# ad_1.net
KiCad netlist of a schematic drawn in Altium Designer
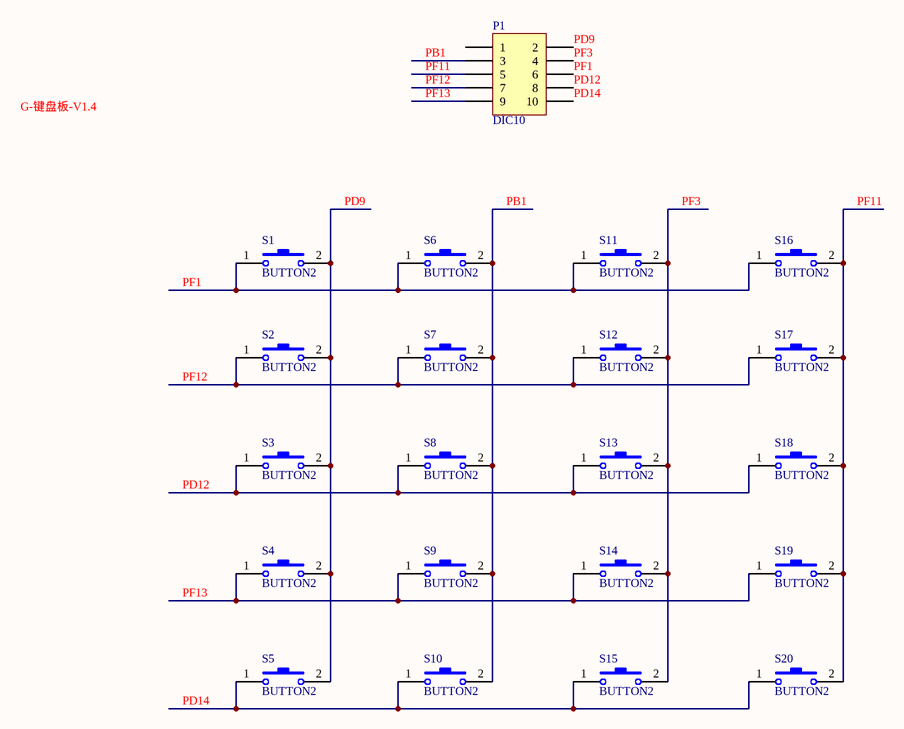
[diagram p0: ad_1.schdoc]

(export (version "E")
  (design (tool "Eeschema 10.0.6"))
  (components
    (comp (ref "P1")
      (value "DIC10")
      (description "连接器")
      (fields (field (name "PUBLISHER") "Altium Limited"))
      (libsource (lib "base") (part "DIC10"))
    )
    (comp (ref "S1")
      (value "BUTTON2")
      (footprint "BUTTON-SMD-7*7")
      (description "按钮")
      (fields (field (name "PUBLISHER") "Altium Limited"))
      (libsource (lib "base") (part "BUTTON2"))
    )
    (comp (ref "S2")
      (value "BUTTON2")
      (footprint "BUTTON-SMD-7*7")
      (description "按钮")
      (fields (field (name "PUBLISHER") "Altium Limited"))
      (libsource (lib "base") (part "BUTTON2"))
    )
    (comp (ref "S3")
      (value "BUTTON2")
      (footprint "BUTTON-SMD-7*7")
      (description "按钮")
      (fields (field (name "PUBLISHER") "Altium Limited"))
      (libsource (lib "base") (part "BUTTON2"))
    )
    (comp (ref "S4")
      (value "BUTTON2")
      (footprint "BUTTON-SMD-7*7")
      (description "按钮")
      (fields (field (name "PUBLISHER") "Altium Limited"))
      (libsource (lib "base") (part "BUTTON2"))
    )
    (comp (ref "S5")
      (value "BUTTON2")
      (footprint "BUTTON-SMD-7*7")
      (description "按钮")
      (fields (field (name "PUBLISHER") "Altium Limited"))
      (libsource (lib "base") (part "BUTTON2"))
    )
    (comp (ref "S6")
      (value "BUTTON2")
      (footprint "BUTTON-SMD-7*7")
      (description "按钮")
      (fields (field (name "PUBLISHER") "Altium Limited"))
      (libsource (lib "base") (part "BUTTON2"))
    )
    (comp (ref "S7")
      (value "BUTTON2")
      (footprint "BUTTON-SMD-7*7")
      (description "按钮")
      (fields (field (name "PUBLISHER") "Altium Limited"))
      (libsource (lib "base") (part "BUTTON2"))
    )
    (comp (ref "S8")
      (value "BUTTON2")
      (footprint "BUTTON-SMD-7*7")
      (description "按钮")
      (fields (field (name "PUBLISHER") "Altium Limited"))
      (libsource (lib "base") (part "BUTTON2"))
    )
    (comp (ref "S9")
      (value "BUTTON2")
      (footprint "BUTTON-SMD-7*7")
      (description "按钮")
      (fields (field (name "PUBLISHER") "Altium Limited"))
      (libsource (lib "base") (part "BUTTON2"))
    )
    (comp (ref "S10")
      (value "BUTTON2")
      (footprint "BUTTON-SMD-7*7")
      (description "按钮")
      (fields (field (name "PUBLISHER") "Altium Limited"))
      (libsource (lib "base") (part "BUTTON2"))
    )
    (comp (ref "S11")
      (value "BUTTON2")
      (footprint "BUTTON-SMD-7*7")
      (description "按钮")
      (fields (field (name "PUBLISHER") "Altium Limited"))
      (libsource (lib "base") (part "BUTTON2"))
    )
    (comp (ref "S12")
      (value "BUTTON2")
      (footprint "BUTTON-SMD-7*7")
      (description "按钮")
      (fields (field (name "PUBLISHER") "Altium Limited"))
      (libsource (lib "base") (part "BUTTON2"))
    )
    (comp (ref "S13")
      (value "BUTTON2")
      (footprint "BUTTON-SMD-7*7")
      (description "按钮")
      (fields (field (name "PUBLISHER") "Altium Limited"))
      (libsource (lib "base") (part "BUTTON2"))
    )
    (comp (ref "S14")
      (value "BUTTON2")
      (footprint "BUTTON-SMD-7*7")
      (description "按钮")
      (fields (field (name "PUBLISHER") "Altium Limited"))
      (libsource (lib "base") (part "BUTTON2"))
    )
    (comp (ref "S15")
      (value "BUTTON2")
      (footprint "BUTTON-SMD-7*7")
      (description "按钮")
      (fields (field (name "PUBLISHER") "Altium Limited"))
      (libsource (lib "base") (part "BUTTON2"))
    )
    (comp (ref "S16")
      (value "BUTTON2")
      (footprint "BUTTON-SMD-7*7")
      (description "按钮")
      (fields (field (name "PUBLISHER") "Altium Limited"))
      (libsource (lib "base") (part "BUTTON2"))
    )
    (comp (ref "S17")
      (value "BUTTON2")
      (footprint "BUTTON-SMD-7*7")
      (description "按钮")
      (fields (field (name "PUBLISHER") "Altium Limited"))
      (libsource (lib "base") (part "BUTTON2"))
    )
    (comp (ref "S18")
      (value "BUTTON2")
      (footprint "BUTTON-SMD-7*7")
      (description "按钮")
      (fields (field (name "PUBLISHER") "Altium Limited"))
      (libsource (lib "base") (part "BUTTON2"))
    )
    (comp (ref "S19")
      (value "BUTTON2")
      (footprint "BUTTON-SMD-7*7")
      (description "按钮")
      (fields (field (name "PUBLISHER") "Altium Limited"))
      (libsource (lib "base") (part "BUTTON2"))
    )
    (comp (ref "S20")
      (value "BUTTON2")
      (footprint "BUTTON-SMD-7*7")
      (description "按钮")
      (fields (field (name "PUBLISHER") "Altium Limited"))
      (libsource (lib "base") (part "BUTTON2"))
    )
  )
  (nets
    (net (code "2") (name "/PB1") (class "Default")
      (node (ref "P1") (pin "3") (pinfunction "3_3") (pintype "passive"))
      (node (ref "S10") (pin "2") (pinfunction "2_2") (pintype "passive"))
      (node (ref "S6") (pin "2") (pinfunction "2_2") (pintype "passive"))
      (node (ref "S7") (pin "2") (pinfunction "2_2") (pintype "passive"))
      (node (ref "S8") (pin "2") (pinfunction "2_2") (pintype "passive"))
      (node (ref "S9") (pin "2") (pinfunction "2_2") (pintype "passive"))
    )
    (net (code "3") (name "/PD9") (class "Default")
      (node (ref "P1") (pin "2") (pinfunction "2_2") (pintype "passive"))
      (node (ref "S1") (pin "2") (pinfunction "2_2") (pintype "passive"))
      (node (ref "S2") (pin "2") (pinfunction "2_2") (pintype "passive"))
      (node (ref "S3") (pin "2") (pinfunction "2_2") (pintype "passive"))
      (node (ref "S4") (pin "2") (pinfunction "2_2") (pintype "passive"))
      (node (ref "S5") (pin "2") (pinfunction "2_2") (pintype "passive"))
    )
    (net (code "4") (name "/PD12") (class "Default")
      (node (ref "P1") (pin "8") (pinfunction "8_8") (pintype "passive"))
      (node (ref "S13") (pin "1") (pinfunction "1_1") (pintype "passive"))
      (node (ref "S18") (pin "1") (pinfunction "1_1") (pintype "passive"))
      (node (ref "S3") (pin "1") (pinfunction "1_1") (pintype "passive"))
      (node (ref "S8") (pin "1") (pinfunction "1_1") (pintype "passive"))
    )
    (net (code "5") (name "/PD14") (class "Default")
      (node (ref "P1") (pin "10") (pinfunction "10_10") (pintype "passive"))
      (node (ref "S10") (pin "1") (pinfunction "1_1") (pintype "passive"))
      (node (ref "S15") (pin "1") (pinfunction "1_1") (pintype "passive"))
      (node (ref "S20") (pin "1") (pinfunction "1_1") (pintype "passive"))
      (node (ref "S5") (pin "1") (pinfunction "1_1") (pintype "passive"))
    )
    (net (code "6") (name "/PF1") (class "Default")
      (node (ref "P1") (pin "6") (pinfunction "6_6") (pintype "passive"))
      (node (ref "S1") (pin "1") (pinfunction "1_1") (pintype "passive"))
      (node (ref "S11") (pin "1") (pinfunction "1_1") (pintype "passive"))
      (node (ref "S16") (pin "1") (pinfunction "1_1") (pintype "passive"))
      (node (ref "S6") (pin "1") (pinfunction "1_1") (pintype "passive"))
    )
    (net (code "7") (name "/PF3") (class "Default")
      (node (ref "P1") (pin "4") (pinfunction "4_4") (pintype "passive"))
      (node (ref "S11") (pin "2") (pinfunction "2_2") (pintype "passive"))
      (node (ref "S12") (pin "2") (pinfunction "2_2") (pintype "passive"))
      (node (ref "S13") (pin "2") (pinfunction "2_2") (pintype "passive"))
      (node (ref "S14") (pin "2") (pinfunction "2_2") (pintype "passive"))
      (node (ref "S15") (pin "2") (pinfunction "2_2") (pintype "passive"))
    )
    (net (code "8") (name "/PF11") (class "Default")
      (node (ref "P1") (pin "5") (pinfunction "5_5") (pintype "passive"))
      (node (ref "S16") (pin "2") (pinfunction "2_2") (pintype "passive"))
      (node (ref "S17") (pin "2") (pinfunction "2_2") (pintype "passive"))
      (node (ref "S18") (pin "2") (pinfunction "2_2") (pintype "passive"))
      (node (ref "S19") (pin "2") (pinfunction "2_2") (pintype "passive"))
      (node (ref "S20") (pin "2") (pinfunction "2_2") (pintype "passive"))
    )
    (net (code "9") (name "/PF12") (class "Default")
      (node (ref "P1") (pin "7") (pinfunction "7_7") (pintype "passive"))
      (node (ref "S12") (pin "1") (pinfunction "1_1") (pintype "passive"))
      (node (ref "S17") (pin "1") (pinfunction "1_1") (pintype "passive"))
      (node (ref "S2") (pin "1") (pinfunction "1_1") (pintype "passive"))
      (node (ref "S7") (pin "1") (pinfunction "1_1") (pintype "passive"))
    )
    (net (code "10") (name "/PF13") (class "Default")
      (node (ref "P1") (pin "9") (pinfunction "9_9") (pintype "passive"))
      (node (ref "S14") (pin "1") (pinfunction "1_1") (pintype "passive"))
      (node (ref "S19") (pin "1") (pinfunction "1_1") (pintype "passive"))
      (node (ref "S4") (pin "1") (pinfunction "1_1") (pintype "passive"))
      (node (ref "S9") (pin "1") (pinfunction "1_1") (pintype "passive"))
    )
    (net (code "11") (name "unconnected-(P1-Pad1)") (class "Default")
      (node (ref "P1") (pin "1") (pinfunction "1_1") (pintype "passive"))
    )
  )
)
